# stm32-shield.net
KiCad netlist of a schematic drawn in EAGLE
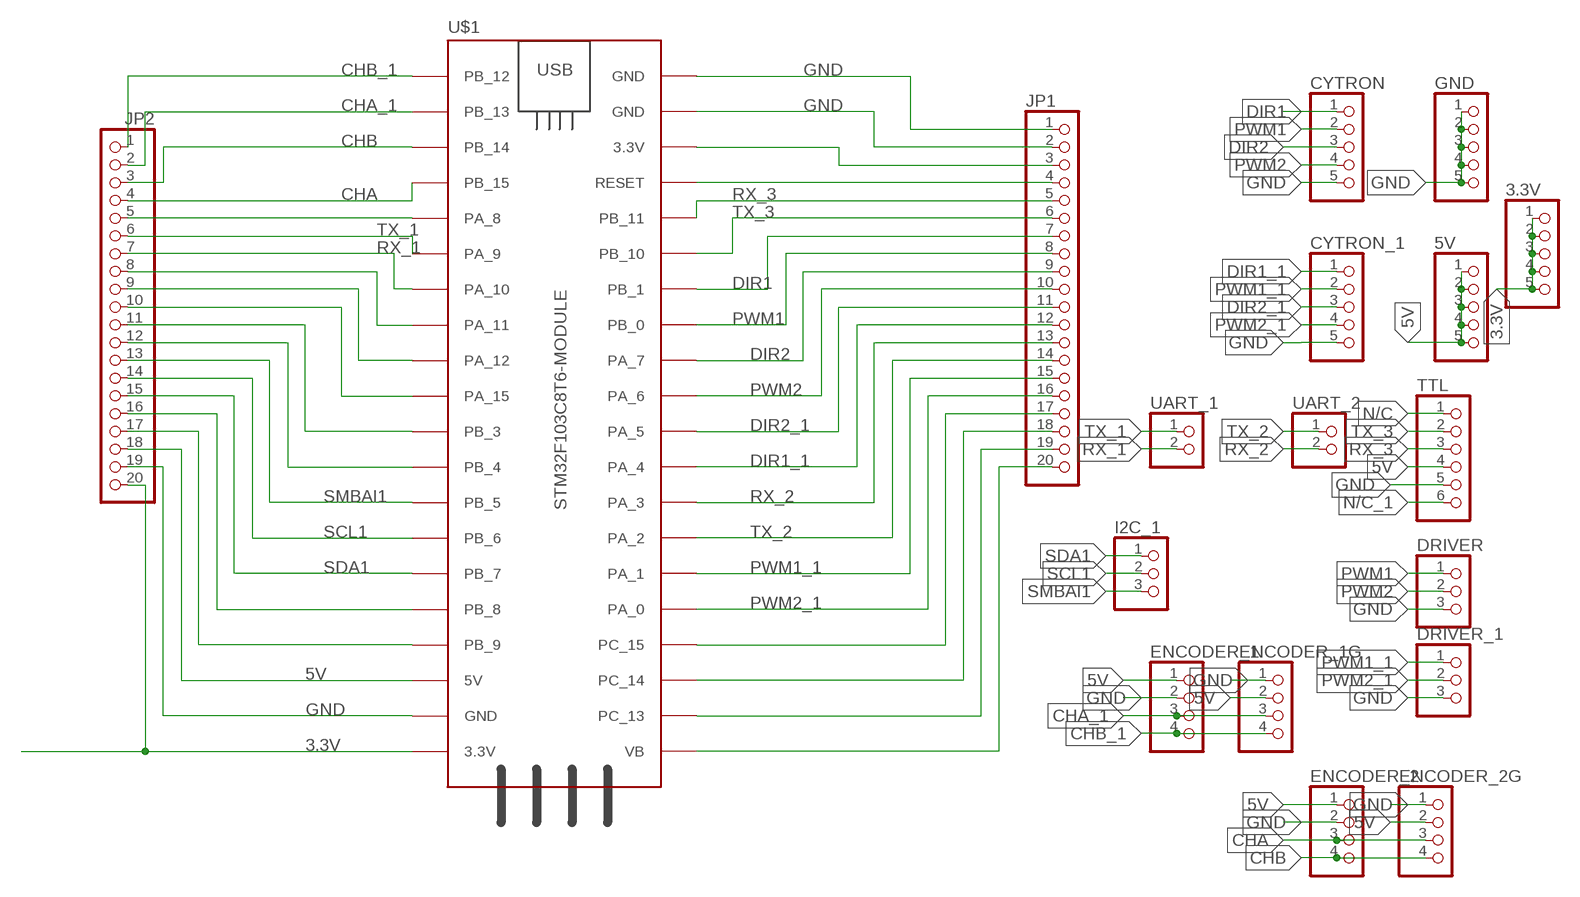
[diagram p0: schematic, sheet 1]

(export (version "E")
  (design (tool "Eeschema 10.0.6"))
  (components
    (comp (ref "3.3V")
      (value "PINHD-1X5")
      (footprint "eagle-import:1X05")
      (libsource (lib "eagle-import") (part "PINHD-1X5"))
    )
    (comp (ref "5V")
      (value "PINHD-1X5")
      (footprint "eagle-import:1X05")
      (libsource (lib "eagle-import") (part "PINHD-1X5"))
    )
    (comp (ref "CYTRON")
      (value "PINHD-1X5")
      (footprint "eagle-import:1X05")
      (libsource (lib "eagle-import") (part "PINHD-1X5"))
    )
    (comp (ref "CYTRON_1")
      (value "PINHD-1X5")
      (footprint "eagle-import:1X05")
      (libsource (lib "eagle-import") (part "PINHD-1X5"))
    )
    (comp (ref "DRIVER")
      (value "PINHD-1X3")
      (footprint "eagle-import:1X03")
      (libsource (lib "eagle-import") (part "PINHD-1X3"))
    )
    (comp (ref "DRIVER_1")
      (value "PINHD-1X3")
      (footprint "eagle-import:1X03")
      (libsource (lib "eagle-import") (part "PINHD-1X3"))
    )
    (comp (ref "ENCODER_1")
      (value "PINHD-1X4")
      (footprint "eagle-import:1X04")
      (libsource (lib "eagle-import") (part "PINHD-1X4"))
    )
    (comp (ref "ENCODER_1G")
      (value "PINHD-1X4")
      (footprint "eagle-import:1X04")
      (libsource (lib "eagle-import") (part "PINHD-1X4"))
    )
    (comp (ref "ENCODER_2")
      (value "PINHD-1X4")
      (footprint "eagle-import:1X04")
      (libsource (lib "eagle-import") (part "PINHD-1X4"))
    )
    (comp (ref "ENCODER_2G")
      (value "PINHD-1X4")
      (footprint "eagle-import:1X04")
      (libsource (lib "eagle-import") (part "PINHD-1X4"))
    )
    (comp (ref "GND")
      (value "PINHD-1X5")
      (footprint "eagle-import:1X05")
      (libsource (lib "eagle-import") (part "PINHD-1X5"))
    )
    (comp (ref "I2C_1")
      (value "PINHD-1X3")
      (footprint "eagle-import:1X03")
      (libsource (lib "eagle-import") (part "PINHD-1X3"))
    )
    (comp (ref "JP1")
      (value "PINHD-1X20")
      (footprint "eagle-import:1X20")
      (libsource (lib "eagle-import") (part "PINHD-1X20"))
    )
    (comp (ref "JP2")
      (value "PINHD-1X20")
      (footprint "eagle-import:1X20")
      (libsource (lib "eagle-import") (part "PINHD-1X20"))
    )
    (comp (ref "TTL")
      (value "PINHD-1X6")
      (footprint "eagle-import:1X06")
      (libsource (lib "eagle-import") (part "PINHD-1X6"))
    )
    (comp (ref "U$1")
      (value "STM32F103C8T6-MODULE")
      (footprint "eagle-import:STM32F103C8T6-MODULE")
      (libsource (lib "eagle-import") (part "STM32F103C8T6-MODULE"))
    )
    (comp (ref "UART_1")
      (value "PINHD-1X2")
      (footprint "eagle-import:1X02")
      (libsource (lib "eagle-import") (part "PINHD-1X2"))
    )
    (comp (ref "UART_2")
      (value "PINHD-1X2")
      (footprint "eagle-import:1X02")
      (libsource (lib "eagle-import") (part "PINHD-1X2"))
    )
  )
  (nets
    (net (code "1") (name "3.3V") (class "Default")
      (node (ref "3.3V") (pin "1") (pinfunction "1_1") (pintype "passive"))
      (node (ref "3.3V") (pin "2") (pinfunction "2_2") (pintype "passive"))
      (node (ref "3.3V") (pin "3") (pinfunction "3_3") (pintype "passive"))
      (node (ref "3.3V") (pin "4") (pinfunction "4_4") (pintype "passive"))
      (node (ref "3.3V") (pin "5") (pinfunction "5_5") (pintype "passive"))
      (node (ref "JP2") (pin "20") (pinfunction "20_20") (pintype "passive"))
      (node (ref "U$1") (pin "3.3V_1") (pinfunction "3.3V_3.3V_1") (pintype "bidirectional"))
    )
    (net (code "2") (name "5V") (class "Default")
      (node (ref "5V") (pin "1") (pinfunction "1_1") (pintype "passive"))
      (node (ref "5V") (pin "2") (pinfunction "2_2") (pintype "passive"))
      (node (ref "5V") (pin "3") (pinfunction "3_3") (pintype "passive"))
      (node (ref "5V") (pin "4") (pinfunction "4_4") (pintype "passive"))
      (node (ref "5V") (pin "5") (pinfunction "5_5") (pintype "passive"))
      (node (ref "ENCODER_1") (pin "1") (pinfunction "1_1") (pintype "passive"))
      (node (ref "ENCODER_1G") (pin "2") (pinfunction "2_2") (pintype "passive"))
      (node (ref "ENCODER_2") (pin "1") (pinfunction "1_1") (pintype "passive"))
      (node (ref "ENCODER_2G") (pin "2") (pinfunction "2_2") (pintype "passive"))
      (node (ref "JP2") (pin "18") (pinfunction "18_18") (pintype "passive"))
      (node (ref "TTL") (pin "4") (pinfunction "4_4") (pintype "passive"))
      (node (ref "U$1") (pin "5V") (pinfunction "5V_5V") (pintype "bidirectional"))
    )
    (net (code "3") (name "CHA") (class "Default")
      (node (ref "ENCODER_2") (pin "3") (pinfunction "3_3") (pintype "passive"))
      (node (ref "ENCODER_2G") (pin "3") (pinfunction "3_3") (pintype "passive"))
      (node (ref "JP2") (pin "4") (pinfunction "4_4") (pintype "passive"))
      (node (ref "U$1") (pin "PB_15") (pinfunction "PB_15_PB_15") (pintype "bidirectional"))
    )
    (net (code "4") (name "CHA_1") (class "Default")
      (node (ref "ENCODER_1") (pin "3") (pinfunction "3_3") (pintype "passive"))
      (node (ref "ENCODER_1G") (pin "3") (pinfunction "3_3") (pintype "passive"))
      (node (ref "JP2") (pin "2") (pinfunction "2_2") (pintype "passive"))
      (node (ref "U$1") (pin "PB_13") (pinfunction "PB_13_PB_13") (pintype "bidirectional"))
    )
    (net (code "5") (name "CHB") (class "Default")
      (node (ref "ENCODER_2") (pin "4") (pinfunction "4_4") (pintype "passive"))
      (node (ref "ENCODER_2G") (pin "4") (pinfunction "4_4") (pintype "passive"))
      (node (ref "JP2") (pin "3") (pinfunction "3_3") (pintype "passive"))
      (node (ref "U$1") (pin "PB_14") (pinfunction "PB_14_PB_14") (pintype "bidirectional"))
    )
    (net (code "6") (name "CHB_1") (class "Default")
      (node (ref "ENCODER_1") (pin "4") (pinfunction "4_4") (pintype "passive"))
      (node (ref "ENCODER_1G") (pin "4") (pinfunction "4_4") (pintype "passive"))
      (node (ref "JP2") (pin "1") (pinfunction "1_1") (pintype "passive"))
      (node (ref "U$1") (pin "PB_12") (pinfunction "PB_12_PB_12") (pintype "bidirectional"))
    )
    (net (code "7") (name "DIR1") (class "Default")
      (node (ref "CYTRON") (pin "1") (pinfunction "1_1") (pintype "passive"))
      (node (ref "JP1") (pin "7") (pinfunction "7_7") (pintype "passive"))
      (node (ref "U$1") (pin "PB_1") (pinfunction "PB_1_PB_1") (pintype "bidirectional"))
    )
    (net (code "8") (name "DIR1_1") (class "Default")
      (node (ref "CYTRON_1") (pin "1") (pinfunction "1_1") (pintype "passive"))
      (node (ref "JP1") (pin "12") (pinfunction "12_12") (pintype "passive"))
      (node (ref "U$1") (pin "PA_4") (pinfunction "PA_4_PA_4") (pintype "bidirectional"))
    )
    (net (code "9") (name "DIR2") (class "Default")
      (node (ref "CYTRON") (pin "3") (pinfunction "3_3") (pintype "passive"))
      (node (ref "JP1") (pin "9") (pinfunction "9_9") (pintype "passive"))
      (node (ref "U$1") (pin "PA_7") (pinfunction "PA_7_PA_7") (pintype "bidirectional"))
    )
    (net (code "10") (name "DIR2_1") (class "Default")
      (node (ref "CYTRON_1") (pin "3") (pinfunction "3_3") (pintype "passive"))
      (node (ref "JP1") (pin "11") (pinfunction "11_11") (pintype "passive"))
      (node (ref "U$1") (pin "PA_5") (pinfunction "PA_5_PA_5") (pintype "bidirectional"))
    )
    (net (code "11") (name "GND") (class "Default")
      (node (ref "CYTRON") (pin "5") (pinfunction "5_5") (pintype "passive"))
      (node (ref "CYTRON_1") (pin "5") (pinfunction "5_5") (pintype "passive"))
      (node (ref "DRIVER") (pin "3") (pinfunction "3_3") (pintype "passive"))
      (node (ref "DRIVER_1") (pin "3") (pinfunction "3_3") (pintype "passive"))
      (node (ref "ENCODER_1") (pin "2") (pinfunction "2_2") (pintype "passive"))
      (node (ref "ENCODER_1G") (pin "1") (pinfunction "1_1") (pintype "passive"))
      (node (ref "ENCODER_2") (pin "2") (pinfunction "2_2") (pintype "passive"))
      (node (ref "ENCODER_2G") (pin "1") (pinfunction "1_1") (pintype "passive"))
      (node (ref "GND") (pin "1") (pinfunction "1_1") (pintype "passive"))
      (node (ref "GND") (pin "2") (pinfunction "2_2") (pintype "passive"))
      (node (ref "GND") (pin "3") (pinfunction "3_3") (pintype "passive"))
      (node (ref "GND") (pin "4") (pinfunction "4_4") (pintype "passive"))
      (node (ref "GND") (pin "5") (pinfunction "5_5") (pintype "passive"))
      (node (ref "JP1") (pin "1") (pinfunction "1_1") (pintype "passive"))
      (node (ref "JP1") (pin "2") (pinfunction "2_2") (pintype "passive"))
      (node (ref "JP2") (pin "19") (pinfunction "19_19") (pintype "passive"))
      (node (ref "TTL") (pin "5") (pinfunction "5_5") (pintype "passive"))
      (node (ref "U$1") (pin "GND_1") (pinfunction "GND_GND_1") (pintype "bidirectional"))
      (node (ref "U$1") (pin "GND_2") (pinfunction "GND_GND_2") (pintype "bidirectional"))
      (node (ref "U$1") (pin "GND_3") (pinfunction "GND_GND_3") (pintype "power_in"))
    )
    (net (code "12") (name "Net-(JP1-Pad3)") (class "Default")
      (node (ref "JP1") (pin "3") (pinfunction "3_3") (pintype "passive"))
      (node (ref "U$1") (pin "3.3V_2") (pinfunction "3.3V_3.3V_2") (pintype "bidirectional"))
    )
    (net (code "13") (name "Net-(JP1-Pad4)") (class "Default")
      (node (ref "JP1") (pin "4") (pinfunction "4_4") (pintype "passive"))
      (node (ref "U$1") (pin "RESET") (pinfunction "RESET_RESET") (pintype "bidirectional"))
    )
    (net (code "14") (name "Net-(JP1-Pad17)") (class "Default")
      (node (ref "JP1") (pin "17") (pinfunction "17_17") (pintype "passive"))
      (node (ref "U$1") (pin "PC_15") (pinfunction "PC_15_PC_15") (pintype "bidirectional"))
    )
    (net (code "15") (name "Net-(JP1-Pad18)") (class "Default")
      (node (ref "JP1") (pin "18") (pinfunction "18_18") (pintype "passive"))
      (node (ref "U$1") (pin "PC_14") (pinfunction "PC_14_PC_14") (pintype "bidirectional"))
    )
    (net (code "16") (name "Net-(JP1-Pad19)") (class "Default")
      (node (ref "JP1") (pin "19") (pinfunction "19_19") (pintype "passive"))
      (node (ref "U$1") (pin "PC_13") (pinfunction "PC_13_PC_13") (pintype "bidirectional"))
    )
    (net (code "17") (name "Net-(JP1-Pad20)") (class "Default")
      (node (ref "JP1") (pin "20") (pinfunction "20_20") (pintype "passive"))
      (node (ref "U$1") (pin "VB") (pinfunction "VB_VB") (pintype "bidirectional"))
    )
    (net (code "18") (name "Net-(JP2-Pad5)") (class "Default")
      (node (ref "JP2") (pin "5") (pinfunction "5_5") (pintype "passive"))
      (node (ref "U$1") (pin "PA_8") (pinfunction "PA_8_PA_8") (pintype "bidirectional"))
    )
    (net (code "19") (name "Net-(JP2-Pad8)") (class "Default")
      (node (ref "JP2") (pin "8") (pinfunction "8_8") (pintype "passive"))
      (node (ref "U$1") (pin "PA_11") (pinfunction "PA_11_PA_11") (pintype "bidirectional"))
    )
    (net (code "20") (name "Net-(JP2-Pad9)") (class "Default")
      (node (ref "JP2") (pin "9") (pinfunction "9_9") (pintype "passive"))
      (node (ref "U$1") (pin "PA_12") (pinfunction "PA_12_PA_12") (pintype "bidirectional"))
    )
    (net (code "21") (name "Net-(JP2-Pad10)") (class "Default")
      (node (ref "JP2") (pin "10") (pinfunction "10_10") (pintype "passive"))
      (node (ref "U$1") (pin "PA_15") (pinfunction "PA_15_PA_15") (pintype "bidirectional"))
    )
    (net (code "22") (name "Net-(JP2-Pad11)") (class "Default")
      (node (ref "JP2") (pin "11") (pinfunction "11_11") (pintype "passive"))
      (node (ref "U$1") (pin "PB_3") (pinfunction "PB_3_PB_3") (pintype "bidirectional"))
    )
    (net (code "23") (name "Net-(JP2-Pad12)") (class "Default")
      (node (ref "JP2") (pin "12") (pinfunction "12_12") (pintype "passive"))
      (node (ref "U$1") (pin "PB_4") (pinfunction "PB_4_PB_4") (pintype "bidirectional"))
    )
    (net (code "24") (name "Net-(JP2-Pad16)") (class "Default")
      (node (ref "JP2") (pin "16") (pinfunction "16_16") (pintype "passive"))
      (node (ref "U$1") (pin "PB_8") (pinfunction "PB_8_PB_8") (pintype "bidirectional"))
    )
    (net (code "25") (name "Net-(JP2-Pad17)") (class "Default")
      (node (ref "JP2") (pin "17") (pinfunction "17_17") (pintype "passive"))
      (node (ref "U$1") (pin "PB_9") (pinfunction "PB_9_PB_9") (pintype "bidirectional"))
    )
    (net (code "26") (name "N{slash}C") (class "Default")
      (node (ref "TTL") (pin "1") (pinfunction "1_1") (pintype "passive"))
    )
    (net (code "27") (name "N{slash}C_1") (class "Default")
      (node (ref "TTL") (pin "6") (pinfunction "6_6") (pintype "passive"))
    )
    (net (code "28") (name "PWM1") (class "Default")
      (node (ref "CYTRON") (pin "2") (pinfunction "2_2") (pintype "passive"))
      (node (ref "DRIVER") (pin "1") (pinfunction "1_1") (pintype "passive"))
      (node (ref "JP1") (pin "8") (pinfunction "8_8") (pintype "passive"))
      (node (ref "U$1") (pin "PB_0") (pinfunction "PB_0_PB_0") (pintype "bidirectional"))
    )
    (net (code "29") (name "PWM1_1") (class "Default")
      (node (ref "CYTRON_1") (pin "2") (pinfunction "2_2") (pintype "passive"))
      (node (ref "DRIVER_1") (pin "1") (pinfunction "1_1") (pintype "passive"))
      (node (ref "JP1") (pin "15") (pinfunction "15_15") (pintype "passive"))
      (node (ref "U$1") (pin "PA_1") (pinfunction "PA_1_PA_1") (pintype "bidirectional"))
    )
    (net (code "30") (name "PWM2") (class "Default")
      (node (ref "CYTRON") (pin "4") (pinfunction "4_4") (pintype "passive"))
      (node (ref "DRIVER") (pin "2") (pinfunction "2_2") (pintype "passive"))
      (node (ref "JP1") (pin "10") (pinfunction "10_10") (pintype "passive"))
      (node (ref "U$1") (pin "PA_6") (pinfunction "PA_6_PA_6") (pintype "bidirectional"))
    )
    (net (code "31") (name "PWM2_1") (class "Default")
      (node (ref "CYTRON_1") (pin "4") (pinfunction "4_4") (pintype "passive"))
      (node (ref "DRIVER_1") (pin "2") (pinfunction "2_2") (pintype "passive"))
      (node (ref "JP1") (pin "16") (pinfunction "16_16") (pintype "passive"))
      (node (ref "U$1") (pin "PA_0") (pinfunction "PA_0_PA_0") (pintype "bidirectional"))
    )
    (net (code "32") (name "RX_1") (class "Default")
      (node (ref "JP2") (pin "7") (pinfunction "7_7") (pintype "passive"))
      (node (ref "U$1") (pin "PA_10") (pinfunction "PA_10_PA_10") (pintype "bidirectional"))
      (node (ref "UART_1") (pin "2") (pinfunction "2_2") (pintype "passive"))
    )
    (net (code "33") (name "RX_2") (class "Default")
      (node (ref "JP1") (pin "13") (pinfunction "13_13") (pintype "passive"))
      (node (ref "U$1") (pin "PA_3") (pinfunction "PA_3_PA_3") (pintype "bidirectional"))
      (node (ref "UART_2") (pin "2") (pinfunction "2_2") (pintype "passive"))
    )
    (net (code "34") (name "RX_3") (class "Default")
      (node (ref "JP1") (pin "5") (pinfunction "5_5") (pintype "passive"))
      (node (ref "TTL") (pin "3") (pinfunction "3_3") (pintype "passive"))
      (node (ref "U$1") (pin "PB_11") (pinfunction "PB_11_PB_11") (pintype "bidirectional"))
    )
    (net (code "35") (name "SCL1") (class "Default")
      (node (ref "I2C_1") (pin "2") (pinfunction "2_2") (pintype "passive"))
      (node (ref "JP2") (pin "14") (pinfunction "14_14") (pintype "passive"))
      (node (ref "U$1") (pin "PB_6") (pinfunction "PB_6_PB_6") (pintype "bidirectional"))
    )
    (net (code "36") (name "SDA1") (class "Default")
      (node (ref "I2C_1") (pin "1") (pinfunction "1_1") (pintype "passive"))
      (node (ref "JP2") (pin "15") (pinfunction "15_15") (pintype "passive"))
      (node (ref "U$1") (pin "PB_7") (pinfunction "PB_7_PB_7") (pintype "bidirectional"))
    )
    (net (code "37") (name "SMBAI1") (class "Default")
      (node (ref "I2C_1") (pin "3") (pinfunction "3_3") (pintype "passive"))
      (node (ref "JP2") (pin "13") (pinfunction "13_13") (pintype "passive"))
      (node (ref "U$1") (pin "PB_5") (pinfunction "PB_5_PB_5") (pintype "bidirectional"))
    )
    (net (code "38") (name "TX_1") (class "Default")
      (node (ref "JP2") (pin "6") (pinfunction "6_6") (pintype "passive"))
      (node (ref "U$1") (pin "PA_9") (pinfunction "PA_9_PA_9") (pintype "bidirectional"))
      (node (ref "UART_1") (pin "1") (pinfunction "1_1") (pintype "passive"))
    )
    (net (code "39") (name "TX_2") (class "Default")
      (node (ref "JP1") (pin "14") (pinfunction "14_14") (pintype "passive"))
      (node (ref "U$1") (pin "PA_2") (pinfunction "PA_2_PA_2") (pintype "bidirectional"))
      (node (ref "UART_2") (pin "1") (pinfunction "1_1") (pintype "passive"))
    )
    (net (code "40") (name "TX_3") (class "Default")
      (node (ref "JP1") (pin "6") (pinfunction "6_6") (pintype "passive"))
      (node (ref "TTL") (pin "2") (pinfunction "2_2") (pintype "passive"))
      (node (ref "U$1") (pin "PB_10") (pinfunction "PB_10_PB_10") (pintype "bidirectional"))
    )
  )
)
